# GPS.net
KiCad netlist of a schematic drawn in Altium Designer
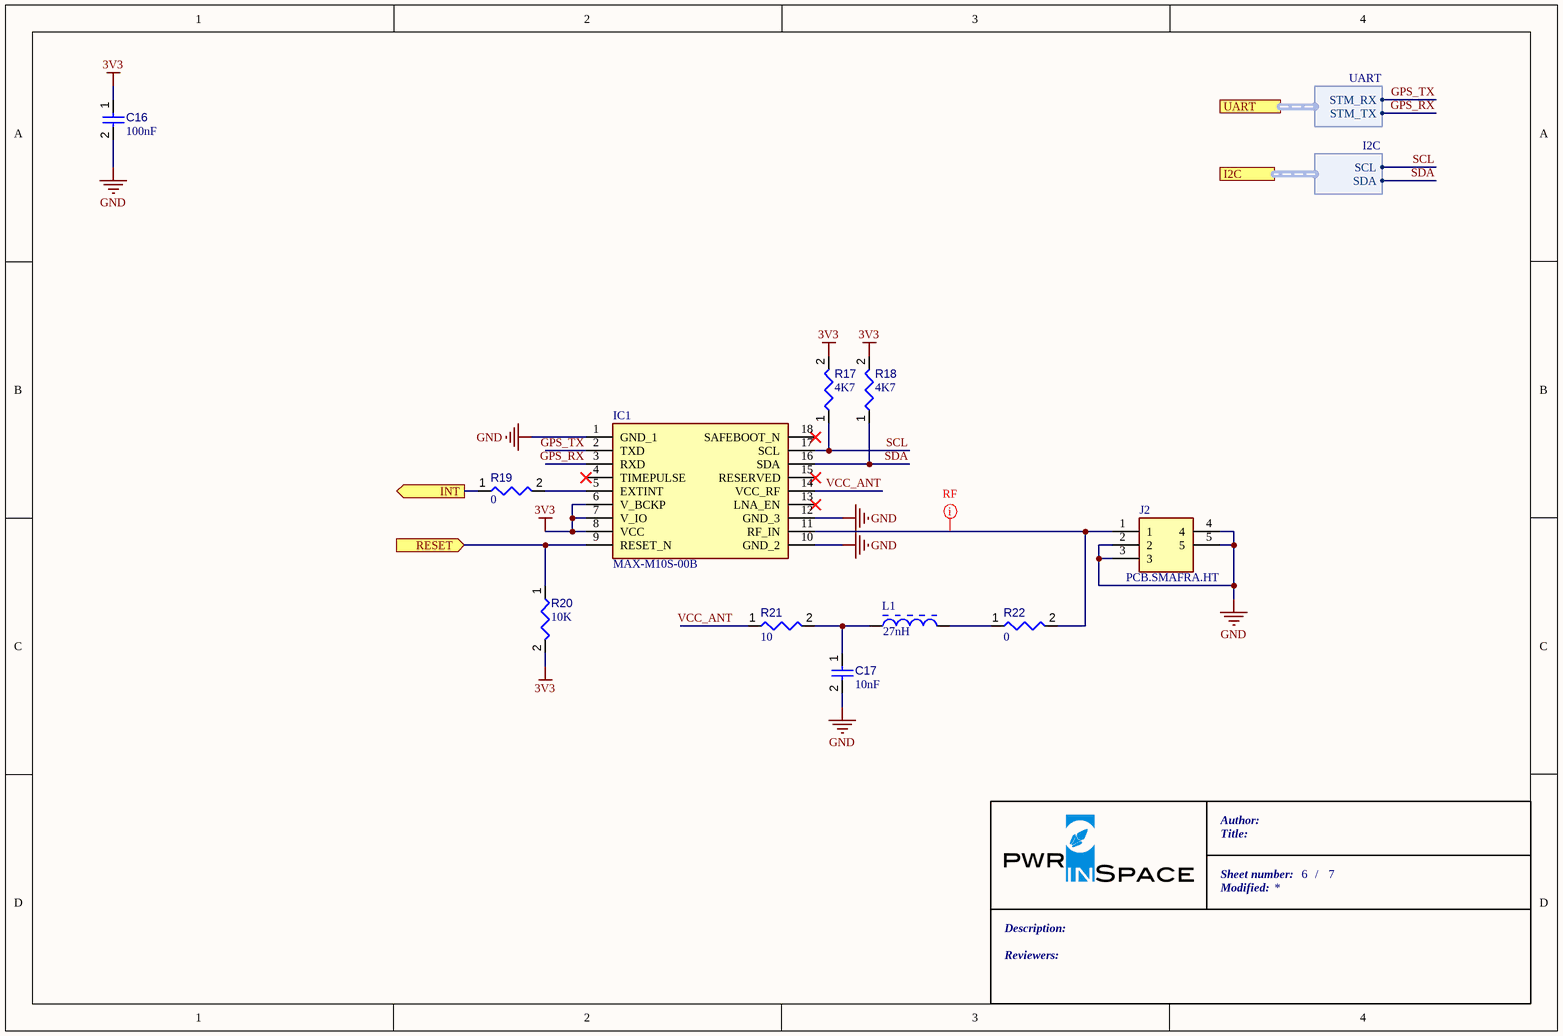
[diagram p0: GPS.SchDoc]

(export (version "E")
  (design (tool "Eeschema 10.0.6"))
  (components
    (comp (ref "C16")
      (value "100nF")
      (footprint "CAPC0805(2012)145_L")
      (description "Chip Capacitor, 100µF +/-20%, 6.3V, 0805, Thickness 1.45 mm")
      (fields (field (name "TOLERANCE") "10%") (field (name "Comment") "Capacitor 100µF +/-20% 6.3V 0805"))
      (libsource (lib "PWr in Space team") (part "CAP-NP-2"))
    )
    (comp (ref "C17")
      (value "10nF")
      (footprint "CAPC0805(2012)145_L")
      (description "Chip Capacitor, 100µF +/-20%, 6.3V, 0805, Thickness 1.45 mm")
      (fields (field (name "TOLERANCE") "10%") (field (name "Comment") "Capacitor 100µF +/-20% 6.3V 0805"))
      (libsource (lib "PWr in Space team") (part "CAP-NP-2"))
    )
    (comp (ref "IC1")
      (value "MAX-M10S-00B")
      (footprint "MAXM10S00B")
      (description "Integrated Circuit")
      (fields (field (name "MOUSER PART NUMBER") "377-MAX-M10S-00B"))
      (libsource (lib "PWr in Space team") (part "MAX-M10S-00B"))
    )
    (comp (ref "J2")
      (value "PCB.SMAFRA.HT")
      (footprint "PCBSMAFRAHT")
      (description "Connector")
      (fields (field (name "MOUSER PART NUMBER") "960-PCB.SMAFRA.HT"))
      (libsource (lib "PWr in Space team") (part "PCB.SMAFRA.HT"))
    )
    (comp (ref "L1")
      (value "27nH")
      (footprint "INDC2013X105X50ML20T20")
      (fields (field (name "TOLERANCE") "25%") (field (name "MANUFACTURER") "Murata"))
      (libsource (lib "PWr in Space team") (part "IND-FB-2"))
    )
    (comp (ref "R17")
      (value "4K7")
      (footprint "RESC0805(2012)_L")
      (description "Chip Resistor, 4,7 Ohms, +/-5 %, 125 mW, -55 to 155 degC, 0805")
      (fields (field (name "TOLERANCE") "5%") (field (name "POWER") "125mW"))
      (libsource (lib "PWr in Space team") (part "RES-2"))
    )
    (comp (ref "R18")
      (value "4K7")
      (footprint "RESC0805(2012)_L")
      (description "Chip Resistor, 4,7 Ohms, +/-5 %, 125 mW, -55 to 155 degC, 0805")
      (fields (field (name "TOLERANCE") "5%") (field (name "POWER") "125mW"))
      (libsource (lib "PWr in Space team") (part "RES-2"))
    )
    (comp (ref "R19")
      (value "0")
      (footprint "RESC0805(2012)_L")
      (description "Chip Resistor, 4,7 Ohms, +/-5 %, 125 mW, -55 to 155 degC, 0805")
      (fields (field (name "TOLERANCE") "5%") (field (name "POWER") "125mW"))
      (libsource (lib "PWr in Space team") (part "RES-2"))
    )
    (comp (ref "R20")
      (value "10K")
      (footprint "RESC0805(2012)_L")
      (description "Chip Resistor, 4,7 Ohms, +/-5 %, 125 mW, -55 to 155 degC, 0805")
      (fields (field (name "TOLERANCE") "5%") (field (name "POWER") "125mW"))
      (libsource (lib "PWr in Space team") (part "RES-2"))
    )
    (comp (ref "R21")
      (value "10")
      (footprint "RESC0805(2012)_L")
      (description "Chip Resistor, 4,7 Ohms, +/-5 %, 125 mW, -55 to 155 degC, 0805")
      (fields (field (name "TOLERANCE") "5%") (field (name "POWER") "125mW"))
      (libsource (lib "PWr in Space team") (part "RES-2"))
    )
    (comp (ref "R22")
      (value "0")
      (footprint "RESC0805(2012)_L")
      (description "Chip Resistor, 4,7 Ohms, +/-5 %, 125 mW, -55 to 155 degC, 0805")
      (fields (field (name "TOLERANCE") "5%") (field (name "POWER") "125mW"))
      (libsource (lib "PWr in Space team") (part "RES-2"))
    )
  )
  (nets
    (net (code "3") (name "/GPS_RX") (class "Default")
      (node (ref "IC1") (pin "3") (pinfunction "RXD_3") (pintype "passive"))
    )
    (net (code "4") (name "/GPS_TX") (class "Default")
      (node (ref "IC1") (pin "2") (pinfunction "TXD_2") (pintype "passive"))
    )
    (net (code "5") (name "/INT") (class "Default")
      (node (ref "R19") (pin "1") (pinfunction "1_1") (pintype "passive"))
    )
    (net (code "6") (name "/RESET") (class "Default")
      (node (ref "IC1") (pin "9") (pinfunction "RESET_N_9") (pintype "passive"))
      (node (ref "R20") (pin "1") (pinfunction "1_1") (pintype "passive"))
    )
    (net (code "7") (name "/SCL") (class "Default")
      (node (ref "IC1") (pin "17") (pinfunction "SCL_17") (pintype "passive"))
      (node (ref "R17") (pin "1") (pinfunction "1_1") (pintype "passive"))
    )
    (net (code "8") (name "/SDA") (class "Default")
      (node (ref "IC1") (pin "16") (pinfunction "SDA_16") (pintype "passive"))
      (node (ref "R18") (pin "1") (pinfunction "1_1") (pintype "passive"))
    )
    (net (code "9") (name "/VCC_ANT") (class "Default")
      (node (ref "IC1") (pin "14") (pinfunction "VCC_RF_14") (pintype "passive"))
      (node (ref "R21") (pin "1") (pinfunction "1_1") (pintype "passive"))
    )
    (net (code "12") (name "3V3") (class "Default")
      (node (ref "C16") (pin "1") (pinfunction "1_1") (pintype "passive"))
      (node (ref "IC1") (pin "6") (pinfunction "V_BCKP_6") (pintype "passive"))
      (node (ref "IC1") (pin "7") (pinfunction "V_IO_7") (pintype "passive"))
      (node (ref "IC1") (pin "8") (pinfunction "VCC_8") (pintype "passive"))
      (node (ref "R17") (pin "2") (pinfunction "2_2") (pintype "passive"))
      (node (ref "R18") (pin "2") (pinfunction "2_2") (pintype "passive"))
      (node (ref "R20") (pin "2") (pinfunction "2_2") (pintype "passive"))
    )
    (net (code "13") (name "GND") (class "Default")
      (node (ref "C16") (pin "2") (pinfunction "2_2") (pintype "passive"))
      (node (ref "C17") (pin "2") (pinfunction "2_2") (pintype "passive"))
      (node (ref "IC1") (pin "1") (pinfunction "GND_1_1") (pintype "passive"))
      (node (ref "IC1") (pin "10") (pinfunction "GND_2_10") (pintype "passive"))
      (node (ref "IC1") (pin "12") (pinfunction "GND_3_12") (pintype "passive"))
      (node (ref "J2") (pin "2") (pinfunction "2_2") (pintype "passive"))
      (node (ref "J2") (pin "3") (pinfunction "3_3") (pintype "passive"))
      (node (ref "J2") (pin "4") (pinfunction "4_4") (pintype "passive"))
      (node (ref "J2") (pin "5") (pinfunction "5_5") (pintype "passive"))
    )
    (net (code "14") (name "Net-(C17-Pad1)") (class "Default")
      (node (ref "C17") (pin "1") (pinfunction "1_1") (pintype "passive"))
      (node (ref "L1") (pin "1") (pinfunction "1_1") (pintype "passive"))
      (node (ref "R21") (pin "2") (pinfunction "2_2") (pintype "passive"))
    )
    (net (code "15") (name "Net-(IC1-EXTINT)") (class "Default")
      (node (ref "IC1") (pin "5") (pinfunction "EXTINT_5") (pintype "passive"))
      (node (ref "R19") (pin "2") (pinfunction "2_2") (pintype "passive"))
    )
    (net (code "16") (name "Net-(IC1-RF_IN)") (class "Default")
      (node (ref "IC1") (pin "11") (pinfunction "RF_IN_11") (pintype "passive"))
      (node (ref "J2") (pin "1") (pinfunction "1_1") (pintype "passive"))
      (node (ref "R22") (pin "2") (pinfunction "2_2") (pintype "passive"))
    )
    (net (code "17") (name "Net-(L1-Pad2)") (class "Default")
      (node (ref "L1") (pin "2") (pinfunction "2_2") (pintype "passive"))
      (node (ref "R22") (pin "1") (pinfunction "1_1") (pintype "passive"))
    )
    (net (code "18") (name "unconnected-(IC1-LNA_EN-Pad13)") (class "Default")
      (node (ref "IC1") (pin "13") (pinfunction "LNA_EN_13") (pintype "passive+no_connect"))
    )
    (net (code "19") (name "unconnected-(IC1-RESERVED-Pad15)") (class "Default")
      (node (ref "IC1") (pin "15") (pinfunction "RESERVED_15") (pintype "passive+no_connect"))
    )
    (net (code "20") (name "unconnected-(IC1-SAFEBOOT_N-Pad18)") (class "Default")
      (node (ref "IC1") (pin "18") (pinfunction "SAFEBOOT_N_18") (pintype "passive+no_connect"))
    )
    (net (code "21") (name "unconnected-(IC1-TIMEPULSE-Pad4)") (class "Default")
      (node (ref "IC1") (pin "4") (pinfunction "TIMEPULSE_4") (pintype "passive+no_connect"))
    )
  )
)
